# mcu0_to_mcu1_isolated_SPI.net
KiCad netlist of a schematic drawn in Altium Designer
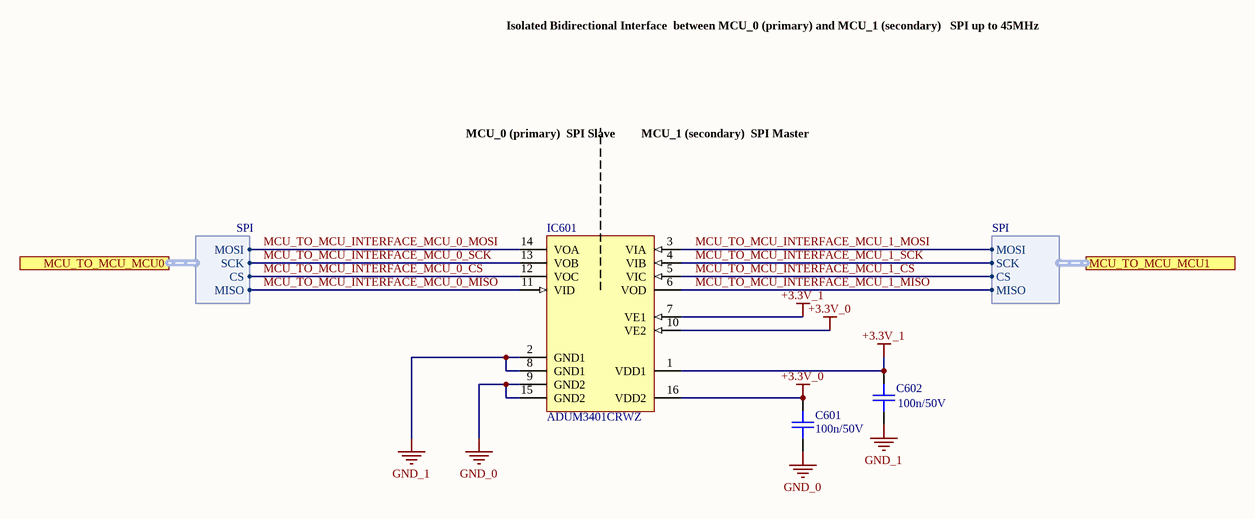
[diagram p0: mcu0_to_mcu1_isolated_SPI.SchDoc]

(export (version "E")
  (design (tool "Eeschema 10.0.6"))
  (components
    (comp (ref "C601")
      (value "100n/50V")
      (footprint "CAPC1608X08N")
      (description "MLCC")
      (fields (field (name "PART NUMBER") "gen_C_ceramic_100n_50V_X7R_0603"))
      (libsource (lib "OE750") (part "C"))
    )
    (comp (ref "C602")
      (value "100n/50V")
      (footprint "CAPC1608X08N")
      (description "MLCC")
      (fields (field (name "PART NUMBER") "gen_C_ceramic_100n_50V_X7R_0603"))
      (libsource (lib "OE750") (part "C"))
    )
    (comp (ref "IC601")
      (value "ADUM3401CRWZ")
      (footprint "ADI-RW-16_N")
      (fields (field (name "MANUFACTURER") "Analog Devices"))
      (libsource (lib "Altium Content Vault") (part "ADI-ADUMX4X1-16"))
    )
  )
  (nets
    (net (code "2") (name "+3.3V_0") (class "Default")
      (node (ref "C601") (pin "2") (pinfunction "2_2") (pintype "passive"))
      (node (ref "IC601") (pin "10") (pinfunction "VE2_10") (pintype "input"))
      (node (ref "IC601") (pin "16") (pinfunction "VDD2_16") (pintype "power_in"))
    )
    (net (code "3") (name "+3.3V_1") (class "Default")
      (node (ref "C602") (pin "1") (pinfunction "1_1") (pintype "passive"))
      (node (ref "IC601") (pin "1") (pinfunction "VDD1_1") (pintype "power_in"))
      (node (ref "IC601") (pin "7") (pinfunction "VE1_7") (pintype "input"))
    )
    (net (code "4") (name "/MCU_TO_MCU_INTERFACE_MCU_0_CS") (class "Default")
      (node (ref "IC601") (pin "12") (pinfunction "VOC_12") (pintype "tri_state"))
    )
    (net (code "5") (name "/MCU_TO_MCU_INTERFACE_MCU_0_MISO") (class "Default")
      (node (ref "IC601") (pin "11") (pinfunction "VID_11") (pintype "input"))
    )
    (net (code "6") (name "/MCU_TO_MCU_INTERFACE_MCU_0_MOSI") (class "Default")
      (node (ref "IC601") (pin "14") (pinfunction "VOA_14") (pintype "tri_state"))
    )
    (net (code "7") (name "/MCU_TO_MCU_INTERFACE_MCU_0_SCK") (class "Default")
      (node (ref "IC601") (pin "13") (pinfunction "VOB_13") (pintype "tri_state"))
    )
    (net (code "8") (name "/MCU_TO_MCU_INTERFACE_MCU_1_CS") (class "Default")
      (node (ref "IC601") (pin "5") (pinfunction "VIC_5") (pintype "input"))
    )
    (net (code "9") (name "/MCU_TO_MCU_INTERFACE_MCU_1_MISO") (class "Default")
      (node (ref "IC601") (pin "6") (pinfunction "VOD_6") (pintype "tri_state"))
    )
    (net (code "10") (name "/MCU_TO_MCU_INTERFACE_MCU_1_MOSI") (class "Default")
      (node (ref "IC601") (pin "3") (pinfunction "VIA_3") (pintype "input"))
    )
    (net (code "11") (name "/MCU_TO_MCU_INTERFACE_MCU_1_SCK") (class "Default")
      (node (ref "IC601") (pin "4") (pinfunction "VIB_4") (pintype "input"))
    )
    (net (code "13") (name "GND_0") (class "Default")
      (node (ref "C601") (pin "1") (pinfunction "1_1") (pintype "passive"))
      (node (ref "IC601") (pin "15") (pinfunction "GND2_15") (pintype "power_in"))
      (node (ref "IC601") (pin "9") (pinfunction "GND2_9") (pintype "power_in"))
    )
    (net (code "14") (name "GND_1") (class "Default")
      (node (ref "C602") (pin "2") (pinfunction "2_2") (pintype "passive"))
      (node (ref "IC601") (pin "2") (pinfunction "GND1_2") (pintype "power_in"))
      (node (ref "IC601") (pin "8") (pinfunction "GND1_8") (pintype "power_in"))
    )
  )
)
